# CP2104SCH.net
KiCad netlist of a schematic drawn in Altium Designer
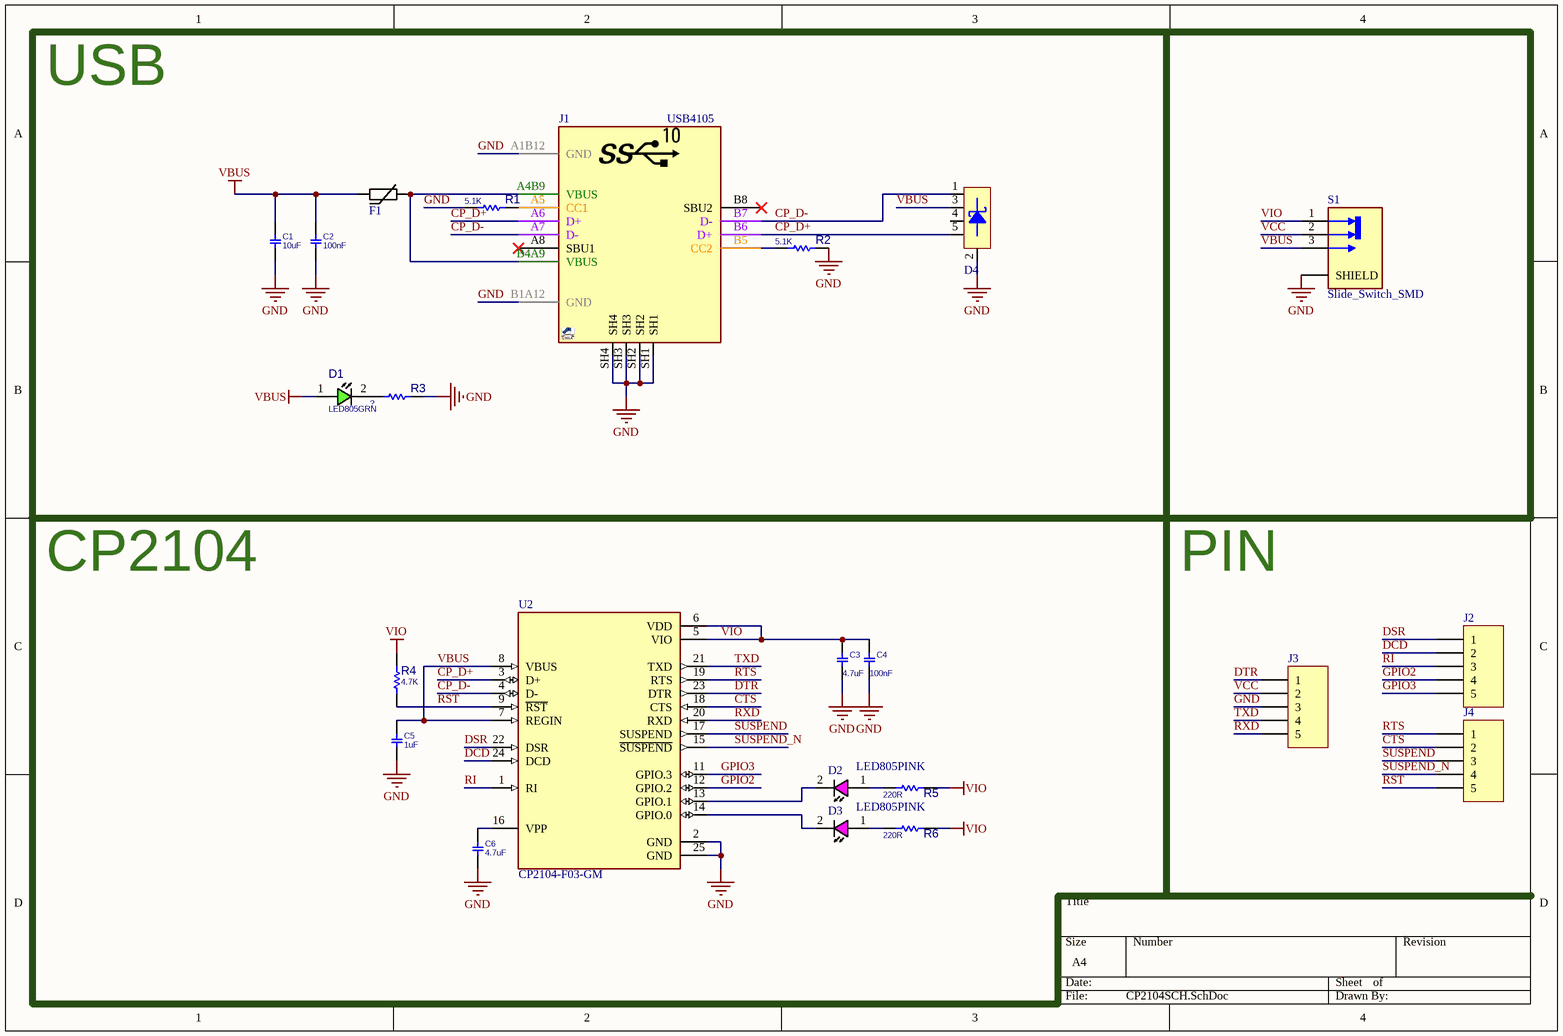
[diagram p0: CP2104SCH.SchDoc]

(export (version "E")
  (design (tool "Eeschema 10.0.6"))
  (components
    (comp (ref "C1")
      (value "10uF")
      (footprint "C0603")
      (description "CAP, MLCC, -F, -V, MATERIAL, -%, 0201")
      (fields (field (name "MANF_P#") "MANF_PART#"))
      (libsource (lib "passive_smd") (part "CAP_SMD_MLCC_0603"))
    )
    (comp (ref "C2")
      (value "100nF")
      (footprint "C0603")
      (description "CAP, MLCC, -F, -V, MATERIAL, -%, 0201")
      (fields (field (name "MANF_P#") "MANF_PART#"))
      (libsource (lib "passive_smd") (part "CAP_SMD_MLCC_0603"))
    )
    (comp (ref "C3")
      (value "4.7uF")
      (footprint "C0603")
      (description "CAP, MLCC, -F, -V, MATERIAL, -%, 0201")
      (fields (field (name "MANF_P#") "MANF_PART#"))
      (libsource (lib "passive_smd") (part "CAP_SMD_MLCC_0603"))
    )
    (comp (ref "C4")
      (value "100nF")
      (footprint "C0603")
      (description "CAP, MLCC, -F, -V, MATERIAL, -%, 0201")
      (fields (field (name "MANF_P#") "MANF_PART#"))
      (libsource (lib "passive_smd") (part "CAP_SMD_MLCC_0603"))
    )
    (comp (ref "C5")
      (value "1uF")
      (footprint "C0603")
      (description "CAP, MLCC, -F, -V, MATERIAL, -%, 0201")
      (fields (field (name "MANF_P#") "MANF_PART#"))
      (libsource (lib "passive_smd") (part "CAP_SMD_MLCC_0603"))
    )
    (comp (ref "C6")
      (value "4.7uF")
      (footprint "C0603")
      (description "CAP, MLCC, -F, -V, MATERIAL, -%, 0201")
      (fields (field (name "MANF_P#") "MANF_PART#"))
      (libsource (lib "passive_smd") (part "CAP_SMD_MLCC_0603"))
    )
    (comp (ref "D1")
      (value "LED805GRN")
      (footprint "LED0805GRN")
      (description "LED, SMD, 0805, GREEN")
      (libsource (lib "led(diode)") (part "LED_SMD_0805_GRN"))
    )
    (comp (ref "D2")
      (value "LED805PINK")
      (footprint "LED_Pink_0805")
      (description "LED, SMD, 0805, PINK")
      (libsource (lib "Mehrdad") (part "LED_Pink"))
    )
    (comp (ref "D3")
      (value "LED805PINK")
      (footprint "LED_Pink_0805")
      (description "LED, SMD, 0805, PINK")
      (libsource (lib "Mehrdad") (part "LED_Pink"))
    )
    (comp (ref "D4")
      (value "SMF-05")
      (footprint "SC70-5_N")
      (description "TVS Diode Array")
      (fields (field (name "VALIDATION") "Valid"))
      (libsource (lib "aKaReZa") (part "Semi_Diod_TVS_SMF05"))
    )
    (comp (ref "F1")
      (value "6V-0.5A")
      (footprint "FUSE0603 (1608)")
      (fields (field (name "PUBLISHER") "Majid Derhambakhsh"))
      (libsource (lib "mBedLab Altium Library (2024-04-20)") (part "PPTC Resettable Fuses"))
    )
    (comp (ref "J1")
      (value "USB4105")
      (footprint "USBC_SMD_16_USB4105")
      (description "CONN, USB, Type C, USB 2.0, Right-Angle, SMD")
      (fields (field (name "MANF") "GCT") (field (name "MANF_P#") "USB4105-GF-A"))
      (libsource (lib "conn_usbc") (part "CONN_USBC_SMD_16_USB4105"))
    )
    (comp (ref "J2")
      (value "5")
      (footprint "HDR_THT_5M_2.54mm")
      (description "Header, single row, 5 pin")
      (fields (field (name "VALIDATION") "NT"))
      (libsource (lib "aKaReZa") (part "Con_MPH_5x1_V_THT_2.54"))
    )
    (comp (ref "J3")
      (value "5")
      (footprint "HDR_THT_5M_2.54mm_RA")
      (description "Header, single row, 5 pin")
      (fields (field (name "VALIDATION") "NT"))
      (libsource (lib "aKaReZa") (part "Con_MPH_5x1_V_THT_2.54"))
    )
    (comp (ref "J4")
      (value "5")
      (footprint "HDR_THT_5M_2.54mm")
      (description "Header, single row, 5 pin")
      (fields (field (name "VALIDATION") "NT"))
      (libsource (lib "aKaReZa") (part "Con_MPH_5x1_V_THT_2.54"))
    )
    (comp (ref "R1")
      (value "5.1K")
      (footprint "R0603")
      (description "RESISTOR, SMD")
      (libsource (lib "passive_smd") (part "RES_SMD_0603"))
    )
    (comp (ref "R2")
      (value "5.1K")
      (footprint "R0603")
      (description "RESISTOR, SMD")
      (libsource (lib "passive_smd") (part "RES_SMD_0603"))
    )
    (comp (ref "R3")
      (value "?")
      (footprint "R0603")
      (description "RESISTOR, SMD")
      (libsource (lib "passive_smd") (part "RES_SMD_0603"))
    )
    (comp (ref "R4")
      (value "4.7K")
      (footprint "R0603")
      (description "RESISTOR, SMD")
      (libsource (lib "passive_smd") (part "RES_SMD_0603"))
    )
    (comp (ref "R5")
      (value "220R")
      (footprint "R0603")
      (description "RESISTOR, SMD")
      (libsource (lib "passive_smd") (part "RES_SMD_0603"))
    )
    (comp (ref "R6")
      (value "220R")
      (footprint "R0603")
      (description "RESISTOR, SMD")
      (libsource (lib "passive_smd") (part "RES_SMD_0603"))
    )
    (comp (ref "S1")
      (value "Slide_Switch_SMD")
      (footprint "Slide_Switch_SMD")
      (libsource (lib "Mehrdad") (part "Slide_Switch_SMD"))
    )
    (comp (ref "U2")
      (value "CP2104-F03-GM")
      (footprint "CP2104-F03-GM")
      (description "USB Bridge, USB to UART USB 2.0 UART Interface 24-QFN _4x4_")
      (libsource (lib "Mehrdad") (part "CP2104-F03-GM"))
    )
  )
  (nets
    (net (code "1") (name "/CP_D+") (class "Default")
      (node (ref "D4") (pin "5") (pinfunction "K_5") (pintype "passive"))
      (node (ref "J1") (pin "A6") (pinfunction "D+_A6") (pintype "passive"))
      (node (ref "J1") (pin "B6") (pinfunction "D+_B6") (pintype "passive"))
      (node (ref "U2") (pin "3") (pinfunction "D+_3") (pintype "bidirectional"))
    )
    (net (code "2") (name "/CP_D-") (class "Default")
      (node (ref "D4") (pin "1") (pinfunction "K_1") (pintype "passive"))
      (node (ref "J1") (pin "A7") (pinfunction "D-_A7") (pintype "passive"))
      (node (ref "J1") (pin "B7") (pinfunction "D-_B7") (pintype "passive"))
      (node (ref "U2") (pin "4") (pinfunction "D-_4") (pintype "bidirectional"))
    )
    (net (code "3") (name "/CTS") (class "Default")
      (node (ref "J4") (pin "2") (pinfunction "2_2") (pintype "passive"))
      (node (ref "U2") (pin "18") (pinfunction "CTS_18") (pintype "input"))
    )
    (net (code "4") (name "/DCD") (class "Default")
      (node (ref "J2") (pin "2") (pinfunction "2_2") (pintype "passive"))
      (node (ref "U2") (pin "24") (pinfunction "DCD_24") (pintype "input"))
    )
    (net (code "5") (name "/DSR") (class "Default")
      (node (ref "J2") (pin "1") (pinfunction "1_1") (pintype "passive"))
      (node (ref "U2") (pin "22") (pinfunction "DSR_22") (pintype "input"))
    )
    (net (code "6") (name "/DTR") (class "Default")
      (node (ref "J3") (pin "1") (pinfunction "1_1") (pintype "passive"))
      (node (ref "U2") (pin "23") (pinfunction "DTR_23") (pintype "output"))
    )
    (net (code "7") (name "/GPIO2") (class "Default")
      (node (ref "J2") (pin "4") (pinfunction "4_4") (pintype "passive"))
      (node (ref "U2") (pin "12") (pinfunction "GPIO.2_12") (pintype "bidirectional"))
    )
    (net (code "8") (name "/GPIO3") (class "Default")
      (node (ref "J2") (pin "5") (pinfunction "5_5") (pintype "passive"))
      (node (ref "U2") (pin "11") (pinfunction "GPIO.3_11") (pintype "bidirectional"))
    )
    (net (code "9") (name "/RI") (class "Default")
      (node (ref "J2") (pin "3") (pinfunction "3_3") (pintype "passive"))
      (node (ref "U2") (pin "1") (pinfunction "RI_1") (pintype "input"))
    )
    (net (code "10") (name "/RST") (class "Default")
      (node (ref "J4") (pin "5") (pinfunction "5_5") (pintype "passive"))
      (node (ref "R4") (pin "1") (pinfunction "1_1") (pintype "passive"))
      (node (ref "U2") (pin "9") (pinfunction "~{RST}_9") (pintype "input"))
    )
    (net (code "11") (name "/RTS") (class "Default")
      (node (ref "J4") (pin "1") (pinfunction "1_1") (pintype "passive"))
      (node (ref "U2") (pin "19") (pinfunction "RTS_19") (pintype "output"))
    )
    (net (code "12") (name "/RXD") (class "Default")
      (node (ref "J3") (pin "5") (pinfunction "5_5") (pintype "passive"))
      (node (ref "U2") (pin "20") (pinfunction "RXD_20") (pintype "input"))
    )
    (net (code "13") (name "/SUSPEND") (class "Default")
      (node (ref "J4") (pin "3") (pinfunction "3_3") (pintype "passive"))
      (node (ref "U2") (pin "17") (pinfunction "SUSPEND_17") (pintype "output"))
    )
    (net (code "14") (name "/SUSPEND_N") (class "Default")
      (node (ref "J4") (pin "4") (pinfunction "4_4") (pintype "passive"))
      (node (ref "U2") (pin "15") (pinfunction "~{SUSPEND}_15") (pintype "output"))
    )
    (net (code "15") (name "/TXD") (class "Default")
      (node (ref "J3") (pin "4") (pinfunction "4_4") (pintype "passive"))
      (node (ref "U2") (pin "21") (pinfunction "TXD_21") (pintype "output"))
    )
    (net (code "16") (name "/VCC") (class "Default")
      (node (ref "J3") (pin "2") (pinfunction "2_2") (pintype "passive"))
      (node (ref "S1") (pin "2") (pinfunction "2_2") (pintype "passive"))
    )
    (net (code "17") (name "GND") (class "Default")
      (node (ref "C1") (pin "1") (pinfunction "1_1") (pintype "passive"))
      (node (ref "C2") (pin "1") (pinfunction "1_1") (pintype "passive"))
      (node (ref "C3") (pin "1") (pinfunction "1_1") (pintype "passive"))
      (node (ref "C4") (pin "1") (pinfunction "1_1") (pintype "passive"))
      (node (ref "C5") (pin "1") (pinfunction "1_1") (pintype "passive"))
      (node (ref "C6") (pin "1") (pinfunction "1_1") (pintype "passive"))
      (node (ref "D4") (pin "2") (pinfunction "K_2") (pintype "passive"))
      (node (ref "J1") (pin "A1B12") (pinfunction "GND_A1B12") (pintype "passive"))
      (node (ref "J1") (pin "B1A12") (pinfunction "GND_B1A12") (pintype "passive"))
      (node (ref "J1") (pin "SH1") (pinfunction "SH1_SH1") (pintype "passive"))
      (node (ref "J1") (pin "SH2") (pinfunction "SH2_SH2") (pintype "passive"))
      (node (ref "J1") (pin "SH3") (pinfunction "SH3_SH3") (pintype "passive"))
      (node (ref "J1") (pin "SH4") (pinfunction "SH4_SH4") (pintype "passive"))
      (node (ref "J3") (pin "3") (pinfunction "3_3") (pintype "passive"))
      (node (ref "R1") (pin "1") (pinfunction "1_1") (pintype "passive"))
      (node (ref "R2") (pin "2") (pinfunction "2_2") (pintype "passive"))
      (node (ref "R3") (pin "1") (pinfunction "1_1") (pintype "passive"))
      (node (ref "S1") (pin "4") (pinfunction "SHIELD_4") (pintype "passive"))
      (node (ref "U2") (pin "2") (pinfunction "GND_2") (pintype "power_in"))
      (node (ref "U2") (pin "25") (pinfunction "GND_25") (pintype "power_in"))
    )
    (net (code "18") (name "Net-(D1-CATHODE)") (class "Default")
      (node (ref "D1") (pin "2") (pinfunction "CATHODE_2") (pintype "passive"))
      (node (ref "R3") (pin "2") (pinfunction "2_2") (pintype "passive"))
    )
    (net (code "19") (name "Net-(D2-ANODE)") (class "Default")
      (node (ref "D2") (pin "1") (pinfunction "ANODE_1") (pintype "passive"))
      (node (ref "R5") (pin "2") (pinfunction "2_2") (pintype "passive"))
    )
    (net (code "20") (name "Net-(D2-CATHODE)") (class "Default")
      (node (ref "D2") (pin "2") (pinfunction "CATHODE_2") (pintype "passive"))
      (node (ref "U2") (pin "13") (pinfunction "GPIO.1_13") (pintype "bidirectional"))
    )
    (net (code "21") (name "Net-(D3-ANODE)") (class "Default")
      (node (ref "D3") (pin "1") (pinfunction "ANODE_1") (pintype "passive"))
      (node (ref "R6") (pin "2") (pinfunction "2_2") (pintype "passive"))
    )
    (net (code "22") (name "Net-(D3-CATHODE)") (class "Default")
      (node (ref "D3") (pin "2") (pinfunction "CATHODE_2") (pintype "passive"))
      (node (ref "U2") (pin "14") (pinfunction "GPIO.0_14") (pintype "bidirectional"))
    )
    (net (code "23") (name "Net-(F1-Pad2)") (class "Default")
      (node (ref "F1") (pin "2") (pinfunction "2_2") (pintype "passive"))
      (node (ref "J1") (pin "A4B9") (pinfunction "VBUS_A4B9") (pintype "passive"))
      (node (ref "J1") (pin "B4A9") (pinfunction "VBUS_B4A9") (pintype "passive"))
    )
    (net (code "24") (name "Net-(J1-CC1)") (class "Default")
      (node (ref "J1") (pin "A5") (pinfunction "CC1_A5") (pintype "passive"))
      (node (ref "R1") (pin "2") (pinfunction "2_2") (pintype "passive"))
    )
    (net (code "25") (name "Net-(J1-CC2)") (class "Default")
      (node (ref "J1") (pin "B5") (pinfunction "CC2_B5") (pintype "passive"))
      (node (ref "R2") (pin "1") (pinfunction "1_1") (pintype "passive"))
    )
    (net (code "26") (name "Net-(U2-VPP)") (class "Default")
      (node (ref "C6") (pin "2") (pinfunction "2_2") (pintype "passive"))
      (node (ref "U2") (pin "16") (pinfunction "VPP_16") (pintype "passive"))
    )
    (net (code "27") (name "VBUS") (class "Default")
      (node (ref "C1") (pin "2") (pinfunction "2_2") (pintype "passive"))
      (node (ref "C2") (pin "2") (pinfunction "2_2") (pintype "passive"))
      (node (ref "C5") (pin "2") (pinfunction "2_2") (pintype "passive"))
      (node (ref "D1") (pin "1") (pinfunction "ANODE_1") (pintype "passive"))
      (node (ref "D4") (pin "3") (pinfunction "K_3") (pintype "passive"))
      (node (ref "F1") (pin "1") (pinfunction "1_1") (pintype "passive"))
      (node (ref "S1") (pin "3") (pinfunction "3_3") (pintype "passive"))
      (node (ref "U2") (pin "7") (pinfunction "REGIN_7") (pintype "input"))
      (node (ref "U2") (pin "8") (pinfunction "VBUS_8") (pintype "input"))
    )
    (net (code "28") (name "VIO") (class "Default")
      (node (ref "C3") (pin "2") (pinfunction "2_2") (pintype "passive"))
      (node (ref "C4") (pin "2") (pinfunction "2_2") (pintype "passive"))
      (node (ref "R4") (pin "2") (pinfunction "2_2") (pintype "passive"))
      (node (ref "R5") (pin "1") (pinfunction "1_1") (pintype "passive"))
      (node (ref "R6") (pin "1") (pinfunction "1_1") (pintype "passive"))
      (node (ref "S1") (pin "1") (pinfunction "1_1") (pintype "passive"))
      (node (ref "U2") (pin "5") (pinfunction "VIO_5") (pintype "power_in"))
      (node (ref "U2") (pin "6") (pinfunction "VDD_6") (pintype "power_in"))
    )
    (net (code "29") (name "unconnected-(D4-K-Pad4)") (class "Default")
      (node (ref "D4") (pin "4") (pinfunction "K_4") (pintype "passive"))
    )
    (net (code "30") (name "unconnected-(J1-SBU1-PadA8)") (class "Default")
      (node (ref "J1") (pin "A8") (pinfunction "SBU1_A8") (pintype "passive+no_connect"))
    )
    (net (code "31") (name "unconnected-(J1-SBU2-PadB8)") (class "Default")
      (node (ref "J1") (pin "B8") (pinfunction "SBU2_B8") (pintype "passive+no_connect"))
    )
  )
)
